# Power.net
KiCad netlist of a schematic drawn in Altium Designer
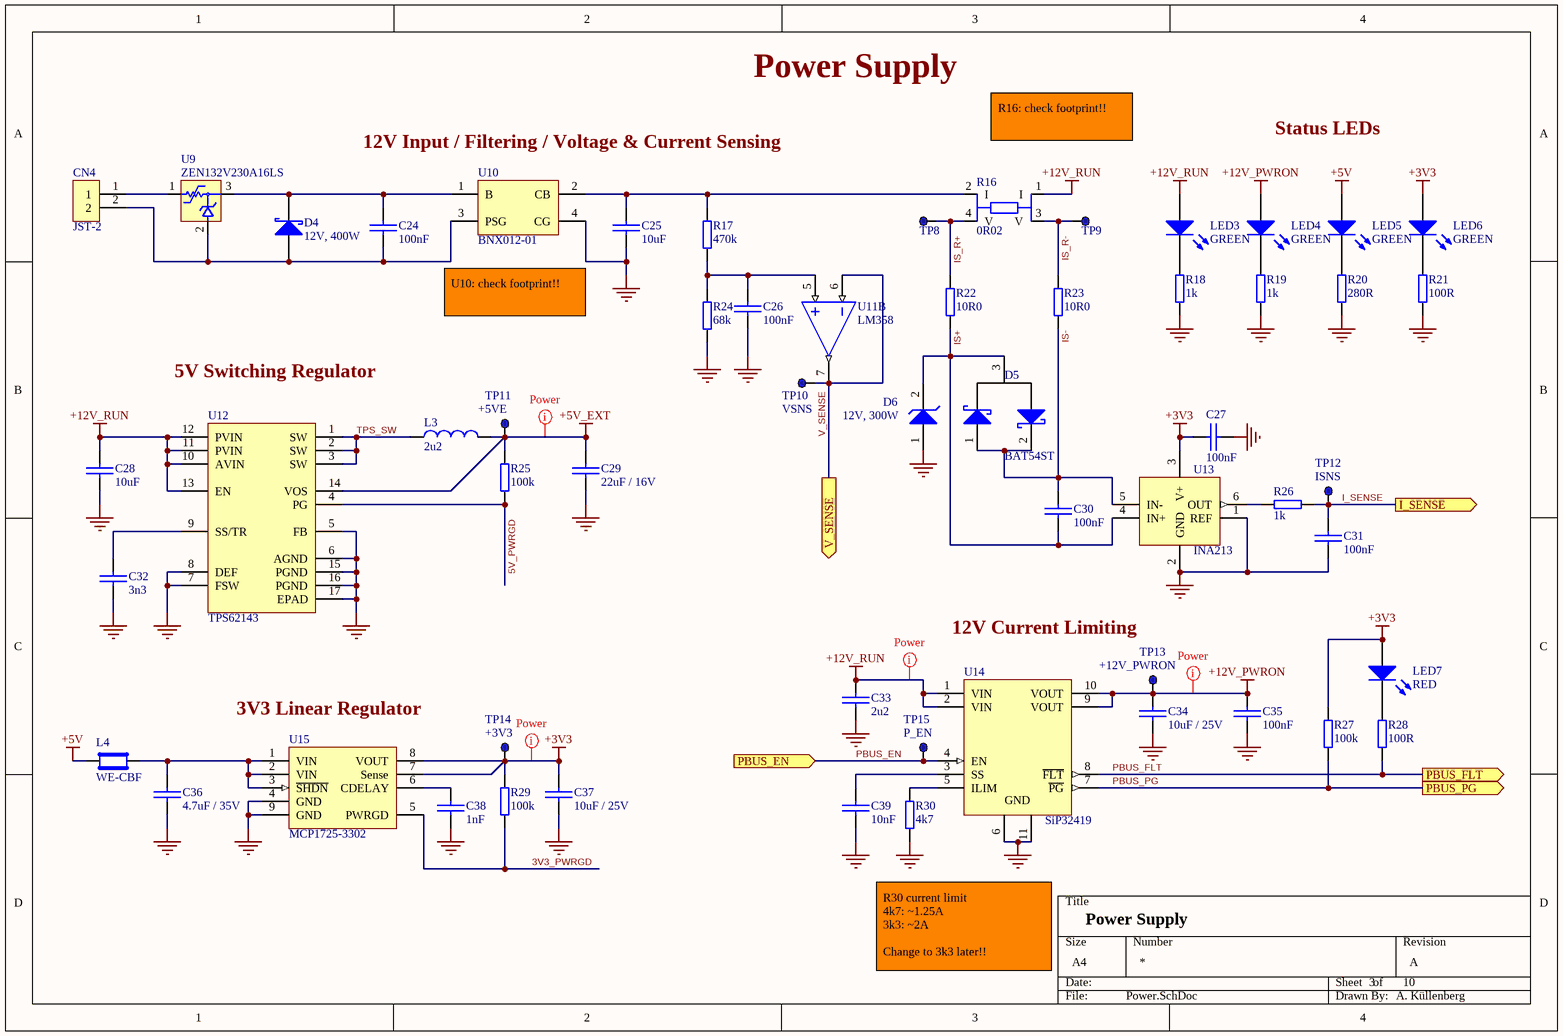
[diagram p0: Power.SchDoc]

(export (version "E")
  (design (tool "Eeschema 10.0.6"))
  (components
    (comp (ref "C24")
      (value "100nF")
      (footprint "C0805")
      (description "CAP CER 0.1UF 50V 10% X7R 0805")
      (fields (field (name "PART NUMBER") "C0805C104K5RACTU") (field (name "MANUFACTURER") "Kemet"))
      (libsource (lib "AKLib") (part "CAP"))
    )
    (comp (ref "C25")
      (value "10uF")
      (footprint "C1206")
      (description "CAP CER 10UF 35V X7R 1206")
      (fields (field (name "PART NUMBER") "GMK316AB7106KL-TR") (field (name "MANUFACTURER") "Taiyo Yuden"))
      (libsource (lib "AKLib") (part "CAP"))
    )
    (comp (ref "C26")
      (value "100nF")
      (footprint "C0603")
      (description "CAP CER 0.1UF 50V X7R 0603")
      (fields (field (name "PART NUMBER") "C0603C104K5RACTU") (field (name "MANUFACTURER") "Kemet"))
      (libsource (lib "AKLib") (part "CAP"))
    )
    (comp (ref "C27")
      (value "100nF")
      (footprint "C0603")
      (description "CAP CER 0.1UF 50V X7R 0603")
      (fields (field (name "PART NUMBER") "C0603C104K5RACTU") (field (name "MANUFACTURER") "Kemet"))
      (libsource (lib "AKLib") (part "CAP"))
    )
    (comp (ref "C28")
      (value "10uF")
      (footprint "C1206")
      (description "CAP CER 10UF 35V X7R 1206")
      (fields (field (name "PART NUMBER") "GMK316AB7106KL-TR") (field (name "MANUFACTURER") "Taiyo Yuden"))
      (libsource (lib "AKLib") (part "CAP"))
    )
    (comp (ref "C29")
      (value "22uF / 16V")
      (footprint "C0805")
      (description "CAP CER 22UF 16V X5R 0805")
      (fields
        (field (name "PART NUMBER") "C2012X5R1C226M085AC")
        (field (name "MANUFACTURER") "TDK Corporation")
      )
      (libsource (lib "AKLib") (part "CAP"))
    )
    (comp (ref "C30")
      (value "100nF")
      (footprint "C0603")
      (description "CAP CER 0.1UF 50V X7R 0603")
      (fields (field (name "PART NUMBER") "C0603C104K5RACTU") (field (name "MANUFACTURER") "Kemet"))
      (libsource (lib "AKLib") (part "CAP"))
    )
    (comp (ref "C31")
      (value "100nF")
      (footprint "C0603")
      (description "CAP CER 0.1UF 50V X7R 0603")
      (fields (field (name "PART NUMBER") "C0603C104K5RACTU") (field (name "MANUFACTURER") "Kemet"))
      (libsource (lib "AKLib") (part "CAP"))
    )
    (comp (ref "C32")
      (value "3n3")
      (footprint "C0603")
      (description "CAP CER 3300PF 50V X7R 0603")
      (fields
        (field (name "PART NUMBER") "CL10B332KB8SFNC")
        (field (name "MANUFACTURER") "Samsung Electro-Mechanics America, Inc.")
      )
      (libsource (lib "AKLib") (part "CAP"))
    )
    (comp (ref "C33")
      (value "2u2")
      (footprint "C0805")
      (description "CAP CER 2.2UF 50V X7R 0805")
      (fields (field (name "PART NUMBER") "UMK212BB7225KG-T") (field (name "MANUFACTURER") "Taiyo Yuden"))
      (libsource (lib "AKLib") (part "CAP"))
    )
    (comp (ref "C34")
      (value "10uF / 25V")
      (footprint "C0603")
      (description "CAP CER 10UF 25V X5R 0603")
      (fields
        (field (name "PART NUMBER") "ZRB18AR61E106ME01L")
        (field (name "MANUFACTURER") "Murata Electronics North America")
      )
      (libsource (lib "AKLib") (part "CAP"))
    )
    (comp (ref "C35")
      (value "100nF")
      (footprint "C0603")
      (description "CAP CER 0.1UF 50V X7R 0603")
      (fields (field (name "PART NUMBER") "C0603C104K5RACTU") (field (name "MANUFACTURER") "Kemet"))
      (libsource (lib "AKLib") (part "CAP"))
    )
    (comp (ref "C36")
      (value "4.7uF / 35V")
      (footprint "C0805")
      (description "CAP CER 4.7UF 35V X7R 0805")
      (fields
        (field (name "PART NUMBER") "C2012X7R1V475K125AE")
        (field (name "MANUFACTURER") "TDK Corporation")
      )
      (libsource (lib "AKLib") (part "CAP"))
    )
    (comp (ref "C37")
      (value "10uF / 25V")
      (footprint "C0603")
      (description "CAP CER 10UF 25V X5R 0603")
      (fields
        (field (name "PART NUMBER") "ZRB18AR61E106ME01L")
        (field (name "MANUFACTURER") "Murata Electronics North America")
      )
      (libsource (lib "AKLib") (part "CAP"))
    )
    (comp (ref "C38")
      (value "1nF")
      (footprint "C0603")
      (description "CAP CER 1000PF 50V X7R 0603")
      (fields (field (name "PART NUMBER") "C0603C102K5RACTU") (field (name "MANUFACTURER") "Kemet"))
      (libsource (lib "AKLib") (part "CAP"))
    )
    (comp (ref "C39")
      (value "10nF")
      (footprint "C0603")
      (description "CAP CER 10000PF 50V X7R 0603")
      (fields (field (name "PART NUMBER") "06035C103KAT2A") (field (name "MANUFACTURER") "AVX Corporation"))
      (libsource (lib "AKLib") (part "CAP"))
    )
    (comp (ref "CN4")
      (value "JST-2")
      (footprint "JST-2")
      (description "CONN HEADER XH TOP 2POS 2.5MM")
      (fields
        (field (name "PART NUMBER") "B2B-XH-A(LF)(SN)")
        (field (name "MANUFACTURER") "JST Sales America Inc.")
      )
      (libsource (lib "AKLib") (part "Header 1x2"))
    )
    (comp (ref "D4")
      (value "12V, 400W")
      (footprint "DO-214AC")
      (description "TVS DIODE 12VWM 25.3VC SMA")
      (fields (field (name "PART NUMBER") "SMAJ12A-TR") (field (name "MANUFACTURER") "STMicroelectronics"))
      (libsource (lib "AKLib") (part "Schottky Diode"))
    )
    (comp (ref "D5")
      (value "BAT54ST")
      (footprint "SOT-523")
      (description "DIODE ARRAY SCHOTTKY 30V SOT523")
      (fields (field (name "PART NUMBER") "BAT54ST-7-F") (field (name "MANUFACTURER") "Diodes Incorporated"))
      (libsource (lib "AKLib") (part "Diode-Dual-Anti"))
    )
    (comp (ref "D6")
      (value "12V, 300W")
      (footprint "SOD523")
      (description "TVS DIODE 12VWM 28VC SOD523")
      (fields (field (name "PART NUMBER") "T12S5-7") (field (name "MANUFACTURER") "Diodes Incorporated"))
      (libsource (lib "AKLib") (part "TVS-Uni"))
    )
    (comp (ref "L3")
      (value "2u2")
      (footprint "IHLP-1212BZ-11")
      (description "FIXED IND 2.2UH 3A 46 MOHM SMD")
      (fields (field (name "PART NUMBER") "IHLP1212BZER2R2M11") (field (name "MANUFACTURER") "Vishay Dale"))
      (libsource (lib "AKLib") (part "IND"))
    )
    (comp (ref "L4")
      (value "WE-CBF")
      (footprint "L0805")
      (description "FERRITE BEAD 600 OHM 0805 1LN")
      (fields (field (name "PART NUMBER") "742792040") (field (name "MANUFACTURER") "Wurth Electronics Inc"))
      (libsource (lib "AKLib") (part "FBEAD"))
    )
    (comp (ref "LED3")
      (value "GREEN")
      (footprint "LED_0603_GREEN")
      (description "LED GREEN CLEAR 0603 SMD")
      (fields (field (name "PART NUMBER") "LTST-C190KGKT") (field (name "MANUFACTURER") "Lite-On Inc."))
      (libsource (lib "AKLib") (part "LED"))
    )
    (comp (ref "LED4")
      (value "GREEN")
      (footprint "LED_0603_GREEN")
      (description "LED GREEN CLEAR 0603 SMD")
      (fields (field (name "PART NUMBER") "LTST-C190KGKT") (field (name "MANUFACTURER") "Lite-On Inc."))
      (libsource (lib "AKLib") (part "LED"))
    )
    (comp (ref "LED5")
      (value "GREEN")
      (footprint "LED_0603_GREEN")
      (description "LED GREEN CLEAR 0603 SMD")
      (fields (field (name "PART NUMBER") "LTST-C190KGKT") (field (name "MANUFACTURER") "Lite-On Inc."))
      (libsource (lib "AKLib") (part "LED"))
    )
    (comp (ref "LED6")
      (value "GREEN")
      (footprint "LED_0603_GREEN")
      (description "LED GREEN CLEAR 0603 SMD")
      (fields (field (name "PART NUMBER") "LTST-C190KGKT") (field (name "MANUFACTURER") "Lite-On Inc."))
      (libsource (lib "AKLib") (part "LED"))
    )
    (comp (ref "LED7")
      (value "RED")
      (footprint "LED_0603_RED")
      (description "LED RED CLEAR 0603 SMD")
      (fields (field (name "PART NUMBER") "LTST-C190KRKT") (field (name "MANUFACTURER") "Lite-On Inc."))
      (libsource (lib "AKLib") (part "LED"))
    )
    (comp (ref "R16")
      (value "0R02")
      (footprint "LVK12")
      (description "RES SMD 0.02 OHM 0.5% 1/2W 1206")
      (fields (field (name "PART NUMBER") "LVK12R020DER") (field (name "MANUFACTURER") "Ohmite"))
      (libsource (lib "AKLib") (part "RES-Kelvin"))
    )
    (comp (ref "R17")
      (value "470k")
      (footprint "R0603")
      (description "RES SMD 470K OHM 1% 1/10W 0603")
      (fields (field (name "PART NUMBER") "RC0603FR-07470KL") (field (name "MANUFACTURER") "Yageo"))
      (libsource (lib "AKLib") (part "RES"))
    )
    (comp (ref "R18")
      (value "1k")
      (footprint "R0603")
      (description "RES SMD 1K OHM 1% 1/10W 0603")
      (fields (field (name "PART NUMBER") "CRCW06031K00FKEA") (field (name "MANUFACTURER") "Vishay Dale"))
      (libsource (lib "AKLib") (part "RES"))
    )
    (comp (ref "R19")
      (value "1k")
      (footprint "R0603")
      (description "RES SMD 1K OHM 1% 1/10W 0603")
      (fields (field (name "PART NUMBER") "CRCW06031K00FKEA") (field (name "MANUFACTURER") "Vishay Dale"))
      (libsource (lib "AKLib") (part "RES"))
    )
    (comp (ref "R20")
      (value "280R")
      (footprint "R0603")
      (description "RES SMD 280 OHM 1% 1/10W 0603")
      (fields (field (name "PART NUMBER") "RC0603FR-07280RL") (field (name "MANUFACTURER") "Yageo"))
      (libsource (lib "AKLib") (part "RES"))
    )
    (comp (ref "R21")
      (value "100R")
      (footprint "R0603")
      (description "RES SMD 100 OHM 5% 1/10W 0603")
      (fields (field (name "PART NUMBER") "RC0603JR-07100RL") (field (name "MANUFACTURER") "Yageo"))
      (libsource (lib "AKLib") (part "RES"))
    )
    (comp (ref "R22")
      (value "10R0")
      (footprint "R0603")
      (description "RES SMD 10 OHM 1% 1/10W 0603")
      (fields (field (name "PART NUMBER") "CRCW060310R0FKEA") (field (name "MANUFACTURER") "Vishay Dale"))
      (libsource (lib "AKLib") (part "RES"))
    )
    (comp (ref "R23")
      (value "10R0")
      (footprint "R0603")
      (description "RES SMD 10 OHM 1% 1/10W 0603")
      (fields (field (name "PART NUMBER") "CRCW060310R0FKEA") (field (name "MANUFACTURER") "Vishay Dale"))
      (libsource (lib "AKLib") (part "RES"))
    )
    (comp (ref "R24")
      (value "68k")
      (footprint "R0603")
      (description "RES SMD 68K OHM 1% 1/10W 0603")
      (fields (field (name "PART NUMBER") "RC0603FR-0768KL") (field (name "MANUFACTURER") "Yageo"))
      (libsource (lib "AKLib") (part "RES"))
    )
    (comp (ref "R25")
      (value "100k")
      (footprint "R0603")
      (description "RES SMD 100K OHM 1% 1/10W 0603")
      (fields (field (name "PART NUMBER") "RC0603FR-07100KL") (field (name "MANUFACTURER") "Yageo"))
      (libsource (lib "AKLib") (part "RES"))
    )
    (comp (ref "R26")
      (value "1k")
      (footprint "R0603")
      (description "RES SMD 1K OHM 1% 1/10W 0603")
      (fields (field (name "PART NUMBER") "CRCW06031K00FKEA") (field (name "MANUFACTURER") "Vishay Dale"))
      (libsource (lib "AKLib") (part "RES"))
    )
    (comp (ref "R27")
      (value "100k")
      (footprint "R0603")
      (description "RES SMD 100K OHM 1% 1/10W 0603")
      (fields (field (name "PART NUMBER") "RC0603FR-07100KL") (field (name "MANUFACTURER") "Yageo"))
      (libsource (lib "AKLib") (part "RES"))
    )
    (comp (ref "R28")
      (value "100R")
      (footprint "R0603")
      (description "RES SMD 100 OHM 5% 1/10W 0603")
      (fields (field (name "PART NUMBER") "RC0603JR-07100RL") (field (name "MANUFACTURER") "Yageo"))
      (libsource (lib "AKLib") (part "RES"))
    )
    (comp (ref "R29")
      (value "100k")
      (footprint "R0603")
      (description "RES SMD 100K OHM 1% 1/10W 0603")
      (fields (field (name "PART NUMBER") "RC0603FR-07100KL") (field (name "MANUFACTURER") "Yageo"))
      (libsource (lib "AKLib") (part "RES"))
    )
    (comp (ref "R30")
      (value "4k7")
      (footprint "R0603")
      (description "RES SMD 4.7K OHM 1% 1/10W 0603")
      (fields (field (name "PART NUMBER") "CRCW06034K70FKEA") (field (name "MANUFACTURER") "Vishay Dale"))
      (libsource (lib "AKLib") (part "RES"))
    )
    (comp (ref "TP8")
      (value "ISR+")
      (footprint "TP_1mm")
      (fields (field (name "PART NUMBER") "TP"))
      (libsource (lib "AKLib") (part "TP"))
    )
    (comp (ref "TP9")
      (value "ISR-")
      (footprint "TP_1mm")
      (fields (field (name "PART NUMBER") "TP"))
      (libsource (lib "AKLib") (part "TP"))
    )
    (comp (ref "TP10")
      (value "VSNS")
      (footprint "TP_1mm")
      (fields (field (name "PART NUMBER") "TP"))
      (libsource (lib "AKLib") (part "TP"))
    )
    (comp (ref "TP11")
      (value "+5VE")
      (footprint "TP_1mm")
      (fields (field (name "PART NUMBER") "TP"))
      (libsource (lib "AKLib") (part "TP"))
    )
    (comp (ref "TP12")
      (value "ISNS")
      (footprint "TP_1mm")
      (fields (field (name "PART NUMBER") "TP"))
      (libsource (lib "AKLib") (part "TP"))
    )
    (comp (ref "TP13")
      (value "+12V_PWRON")
      (footprint "TP_1mm")
      (fields (field (name "PART NUMBER") "TP"))
      (libsource (lib "AKLib") (part "TP"))
    )
    (comp (ref "TP14")
      (value "+3V3")
      (footprint "TP_1mm")
      (fields (field (name "PART NUMBER") "TP"))
      (libsource (lib "AKLib") (part "TP"))
    )
    (comp (ref "TP15")
      (value "P_EN")
      (footprint "TP_1mm")
      (fields (field (name "PART NUMBER") "TP"))
      (libsource (lib "AKLib") (part "TP"))
    )
    (comp (ref "U9")
      (value "ZEN132V230A16LS")
      (footprint "ZEN132V230A16LS")
      (description "POLYZEN 13.2V PPTC/ZENER SMD")
      (fields (field (name "MANUFACTURER") "Littelfuse Inc."))
      (libsource (lib "AKLib") (part "PolyZen"))
    )
    (comp (ref "U10")
      (value "BNX012-01")
      (footprint "BNX012-01")
      (description "FILTER LC TH")
      (fields (field (name "MANUFACTURER") "Murata Electronics North America"))
      (libsource (lib "AKLib") (part "BNX012-01"))
    )
    (comp (ref "U11")
      (value "LM358")
      (footprint "DFN 2x2_LM358")
      (description "IC OPAMP GP 1.1MHZ 8DFN")
      (fields (field (name "PART NUMBER") "LM358QT") (field (name "MANUFACTURER") "STMicroelectronics"))
      (libsource (lib "AKLib") (part "LM358"))
    )
    (comp (ref "U12")
      (value "TPS62143")
      (footprint "RGT0016C")
      (description "IC REG BUCK 5V 2A SYNC 16QFN")
      (fields (field (name "PART NUMBER") "TPS62143RGTR") (field (name "MANUFACTURER") "Texas Instruments"))
      (libsource (lib "AKLib") (part "TPS6214x"))
    )
    (comp (ref "U13")
      (value "INA213")
      (footprint "SC-70-6")
      (description "IC OPAMP CURR SENSE 14KHZ SC70-6")
      (fields (field (name "PART NUMBER") "INA213BIDCKR") (field (name "MANUFACTURER") "Texas Instruments"))
      (libsource (lib "AKLib") (part "INA21x"))
    )
    (comp (ref "U14")
      (value "SiP32419")
      (footprint "DFN 3x3_SiP324x9")
      (description "LOAD SWITCH 3A 28V 10DFN")
      (fields
        (field (name "PART NUMBER") "SIP32419DN-T1-GE4")
        (field (name "MANUFACTURER") "Vishay Siliconix")
      )
      (libsource (lib "AKLib") (part "SiP324x9"))
    )
    (comp (ref "U15")
      (value "MCP1725-3302")
      (footprint "QFN50P200X300X100_HS-9N")
      (description "IC REG LDO 3.3V 0.5A 8DFN")
      (fields
        (field (name "PART NUMBER") "MCP1725-3302E/MC")
        (field (name "MANUFACTURER") "Microchip Technology")
      )
      (libsource (lib "AKLib") (part "MCP1725_fixed"))
    )
  )
  (nets
    (net (code "1") (name "+3V3") (class "Default")
      (node (ref "C27") (pin "1") (pinfunction "1_1") (pintype "passive"))
      (node (ref "C37") (pin "2") (pinfunction "2_2") (pintype "passive"))
      (node (ref "LED6") (pin "1") (pinfunction "A_1") (pintype "passive"))
      (node (ref "LED7") (pin "1") (pinfunction "A_1") (pintype "passive"))
      (node (ref "R27") (pin "2") (pinfunction "2_2") (pintype "passive"))
      (node (ref "R29") (pin "2") (pinfunction "2_2") (pintype "passive"))
      (node (ref "TP14") (pin "1") (pinfunction "1_1") (pintype "passive"))
      (node (ref "U13") (pin "3") (pinfunction "V+_3") (pintype "power_in"))
      (node (ref "U15") (pin "7") (pinfunction "Sense_7") (pintype "passive"))
      (node (ref "U15") (pin "8") (pinfunction "VOUT_8") (pintype "power_in"))
    )
    (net (code "2") (name "+5V") (class "Default")
      (node (ref "L4") (pin "1") (pinfunction "1_1") (pintype "passive"))
      (node (ref "LED5") (pin "1") (pinfunction "A_1") (pintype "passive"))
    )
    (net (code "3") (name "+5V_EXT") (class "Default")
      (node (ref "C29") (pin "2") (pinfunction "2_2") (pintype "passive"))
      (node (ref "L3") (pin "2") (pinfunction "2_2") (pintype "passive"))
      (node (ref "R25") (pin "2") (pinfunction "2_2") (pintype "passive"))
      (node (ref "TP11") (pin "1") (pinfunction "1_1") (pintype "passive"))
      (node (ref "U12") (pin "14") (pinfunction "VOS_14") (pintype "passive"))
    )
    (net (code "4") (name "+12V_PWRON") (class "Default")
      (node (ref "C34") (pin "2") (pinfunction "2_2") (pintype "passive"))
      (node (ref "C35") (pin "2") (pinfunction "2_2") (pintype "passive"))
      (node (ref "LED4") (pin "1") (pinfunction "A_1") (pintype "passive"))
      (node (ref "TP13") (pin "1") (pinfunction "1_1") (pintype "passive"))
      (node (ref "U14") (pin "10") (pinfunction "VOUT_10") (pintype "power_in"))
      (node (ref "U14") (pin "9") (pinfunction "VOUT_9") (pintype "power_in"))
    )
    (net (code "5") (name "+12V_RUN") (class "Default")
      (node (ref "C28") (pin "2") (pinfunction "2_2") (pintype "passive"))
      (node (ref "C33") (pin "2") (pinfunction "2_2") (pintype "passive"))
      (node (ref "LED3") (pin "1") (pinfunction "A_1") (pintype "passive"))
      (node (ref "R16") (pin "1") (pinfunction "I_1") (pintype "passive"))
      (node (ref "U12") (pin "10") (pinfunction "AVIN_10") (pintype "passive"))
      (node (ref "U12") (pin "11") (pinfunction "PVIN_11") (pintype "passive"))
      (node (ref "U12") (pin "12") (pinfunction "PVIN_12") (pintype "passive"))
      (node (ref "U12") (pin "13") (pinfunction "EN_13") (pintype "passive"))
      (node (ref "U14") (pin "1") (pinfunction "VIN_1") (pintype "power_in"))
      (node (ref "U14") (pin "2") (pinfunction "VIN_2") (pintype "power_in"))
    )
    (net (code "6") (name "/3V3_PWRGD") (class "Default")
      (node (ref "R29") (pin "1") (pinfunction "1_1") (pintype "passive"))
      (node (ref "U15") (pin "5") (pinfunction "PWRGD_5") (pintype "open_collector"))
    )
    (net (code "7") (name "/5V_PWRGD") (class "Default")
      (node (ref "R25") (pin "1") (pinfunction "1_1") (pintype "passive"))
      (node (ref "U12") (pin "4") (pinfunction "PG_4") (pintype "passive"))
    )
    (net (code "8") (name "/IS+") (class "Default")
      (node (ref "C30") (pin "1") (pinfunction "1_1") (pintype "passive"))
      (node (ref "D5") (pin "3") (pinfunction "COM_3") (pintype "passive"))
      (node (ref "D6") (pin "2") (pinfunction "K_2") (pintype "passive"))
      (node (ref "R22") (pin "1") (pinfunction "1_1") (pintype "passive"))
      (node (ref "U13") (pin "4") (pinfunction "IN+_4") (pintype "passive"))
    )
    (net (code "9") (name "/IS-") (class "Default")
      (node (ref "C30") (pin "2") (pinfunction "2_2") (pintype "passive"))
      (node (ref "D5") (pin "1") (pinfunction "A_1") (pintype "passive"))
      (node (ref "D5") (pin "2") (pinfunction "K_2") (pintype "passive"))
      (node (ref "R23") (pin "1") (pinfunction "1_1") (pintype "passive"))
      (node (ref "U13") (pin "5") (pinfunction "IN-_5") (pintype "passive"))
    )
    (net (code "10") (name "/IS_R+") (class "Default")
      (node (ref "R16") (pin "4") (pinfunction "V_4") (pintype "power_in"))
      (node (ref "R22") (pin "2") (pinfunction "2_2") (pintype "passive"))
      (node (ref "TP8") (pin "1") (pinfunction "1_1") (pintype "passive"))
    )
    (net (code "11") (name "/IS_R-") (class "Default")
      (node (ref "R16") (pin "3") (pinfunction "V_3") (pintype "power_in"))
      (node (ref "R23") (pin "2") (pinfunction "2_2") (pintype "passive"))
      (node (ref "TP9") (pin "1") (pinfunction "1_1") (pintype "passive"))
    )
    (net (code "12") (name "/I_SENSE") (class "Default")
      (node (ref "C31") (pin "2") (pinfunction "2_2") (pintype "passive"))
      (node (ref "R26") (pin "2") (pinfunction "2_2") (pintype "passive"))
      (node (ref "TP12") (pin "1") (pinfunction "1_1") (pintype "passive"))
    )
    (net (code "13") (name "/PBUS_EN") (class "Default")
      (node (ref "TP15") (pin "1") (pinfunction "1_1") (pintype "passive"))
      (node (ref "U14") (pin "4") (pinfunction "EN_4") (pintype "input"))
    )
    (net (code "14") (name "/PBUS_FLT") (class "Default")
      (node (ref "R28") (pin "1") (pinfunction "1_1") (pintype "passive"))
      (node (ref "U14") (pin "8") (pinfunction "~{FLT}_8") (pintype "output"))
    )
    (net (code "15") (name "/PBUS_PG") (class "Default")
      (node (ref "R27") (pin "1") (pinfunction "1_1") (pintype "passive"))
      (node (ref "U14") (pin "7") (pinfunction "~{PG}_7") (pintype "output"))
    )
    (net (code "16") (name "/TPS_SW") (class "Default")
      (node (ref "L3") (pin "1") (pinfunction "1_1") (pintype "passive"))
      (node (ref "U12") (pin "1") (pinfunction "SW_1") (pintype "passive"))
      (node (ref "U12") (pin "2") (pinfunction "SW_2") (pintype "passive"))
      (node (ref "U12") (pin "3") (pinfunction "SW_3") (pintype "passive"))
    )
    (net (code "17") (name "/V_SENSE") (class "Default")
      (node (ref "TP10") (pin "1") (pinfunction "1_1") (pintype "passive"))
      (node (ref "U11") (pin "6") (pinfunction "IN-_6") (pintype "input"))
      (node (ref "U11") (pin "7") (pinfunction "OUT_7") (pintype "output"))
    )
    (net (code "18") (name "GND") (class "Default")
      (node (ref "C25") (pin "1") (pinfunction "1_1") (pintype "passive"))
      (node (ref "C26") (pin "1") (pinfunction "1_1") (pintype "passive"))
      (node (ref "C27") (pin "2") (pinfunction "2_2") (pintype "passive"))
      (node (ref "C28") (pin "1") (pinfunction "1_1") (pintype "passive"))
      (node (ref "C29") (pin "1") (pinfunction "1_1") (pintype "passive"))
      (node (ref "C31") (pin "1") (pinfunction "1_1") (pintype "passive"))
      (node (ref "C32") (pin "1") (pinfunction "1_1") (pintype "passive"))
      (node (ref "C33") (pin "1") (pinfunction "1_1") (pintype "passive"))
      (node (ref "C34") (pin "1") (pinfunction "1_1") (pintype "passive"))
      (node (ref "C35") (pin "1") (pinfunction "1_1") (pintype "passive"))
      (node (ref "C36") (pin "1") (pinfunction "1_1") (pintype "passive"))
      (node (ref "C37") (pin "1") (pinfunction "1_1") (pintype "passive"))
      (node (ref "C38") (pin "1") (pinfunction "1_1") (pintype "passive"))
      (node (ref "C39") (pin "1") (pinfunction "1_1") (pintype "passive"))
      (node (ref "D6") (pin "1") (pinfunction "A_1") (pintype "passive"))
      (node (ref "R18") (pin "1") (pinfunction "1_1") (pintype "passive"))
      (node (ref "R19") (pin "1") (pinfunction "1_1") (pintype "passive"))
      (node (ref "R20") (pin "1") (pinfunction "1_1") (pintype "passive"))
      (node (ref "R21") (pin "1") (pinfunction "1_1") (pintype "passive"))
      (node (ref "R24") (pin "1") (pinfunction "1_1") (pintype "passive"))
      (node (ref "R30") (pin "1") (pinfunction "1_1") (pintype "passive"))
      (node (ref "U10") (pin "4") (pinfunction "CG_4") (pintype "passive"))
      (node (ref "U12") (pin "15") (pinfunction "PGND_15") (pintype "passive"))
      (node (ref "U12") (pin "16") (pinfunction "PGND_16") (pintype "passive"))
      (node (ref "U12") (pin "17") (pinfunction "EPAD_17") (pintype "passive"))
      (node (ref "U12") (pin "5") (pinfunction "FB_5") (pintype "passive"))
      (node (ref "U12") (pin "6") (pinfunction "AGND_6") (pintype "passive"))
      (node (ref "U12") (pin "7") (pinfunction "FSW_7") (pintype "passive"))
      (node (ref "U12") (pin "8") (pinfunction "DEF_8") (pintype "passive"))
      (node (ref "U13") (pin "1") (pinfunction "REF_1") (pintype "passive"))
      (node (ref "U13") (pin "2") (pinfunction "GND_2") (pintype "power_in"))
      (node (ref "U14") (pin "11") (pinfunction "GND_11") (pintype "power_in"))
      (node (ref "U14") (pin "6") (pinfunction "GND_6") (pintype "power_in"))
      (node (ref "U15") (pin "4") (pinfunction "GND_4") (pintype "power_in"))
      (node (ref "U15") (pin "9") (pinfunction "GND_9") (pintype "power_in"))
    )
    (net (code "19") (name "Net-(CN4-Pad1)") (class "Default")
      (node (ref "CN4") (pin "1") (pinfunction "1_1") (pintype "passive"))
      (node (ref "U9") (pin "1") (pintype "passive"))
    )
    (net (code "20") (name "Net-(D4-A)") (class "Default")
      (node (ref "C24") (pin "1") (pinfunction "1_1") (pintype "passive"))
      (node (ref "CN4") (pin "2") (pinfunction "2_2") (pintype "passive"))
      (node (ref "D4") (pin "1") (pinfunction "A_1") (pintype "passive"))
      (node (ref "U10") (pin "3") (pinfunction "PSG_3") (pintype "passive"))
      (node (ref "U9") (pin "2") (pintype "passive"))
    )
    (net (code "21") (name "Net-(D4-K)") (class "Default")
      (node (ref "C24") (pin "2") (pinfunction "2_2") (pintype "passive"))
      (node (ref "D4") (pin "2") (pinfunction "K_2") (pintype "passive"))
      (node (ref "U10") (pin "1") (pinfunction "B_1") (pintype "passive"))
      (node (ref "U9") (pin "3") (pintype "passive"))
    )
    (net (code "22") (name "Net-(LED3-K)") (class "Default")
      (node (ref "LED3") (pin "2") (pinfunction "K_2") (pintype "passive"))
      (node (ref "R18") (pin "2") (pinfunction "2_2") (pintype "passive"))
    )
    (net (code "23") (name "Net-(LED4-K)") (class "Default")
      (node (ref "LED4") (pin "2") (pinfunction "K_2") (pintype "passive"))
      (node (ref "R19") (pin "2") (pinfunction "2_2") (pintype "passive"))
    )
    (net (code "24") (name "Net-(LED5-K)") (class "Default")
      (node (ref "LED5") (pin "2") (pinfunction "K_2") (pintype "passive"))
      (node (ref "R20") (pin "2") (pinfunction "2_2") (pintype "passive"))
    )
    (net (code "25") (name "Net-(LED6-K)") (class "Default")
      (node (ref "LED6") (pin "2") (pinfunction "K_2") (pintype "passive"))
      (node (ref "R21") (pin "2") (pinfunction "2_2") (pintype "passive"))
    )
    (net (code "26") (name "Net-(LED7-K)") (class "Default")
      (node (ref "LED7") (pin "2") (pinfunction "K_2") (pintype "passive"))
      (node (ref "R28") (pin "2") (pinfunction "2_2") (pintype "passive"))
    )
    (net (code "27") (name "Net-(U10-CB)") (class "Default")
      (node (ref "C25") (pin "2") (pinfunction "2_2") (pintype "passive"))
      (node (ref "R16") (pin "2") (pinfunction "I_2") (pintype "passive"))
      (node (ref "R17") (pin "2") (pinfunction "2_2") (pintype "passive"))
      (node (ref "U10") (pin "2") (pinfunction "CB_2") (pintype "passive"))
    )
    (net (code "28") (name "Net-(U11B-IN+)") (class "Default")
      (node (ref "C26") (pin "2") (pinfunction "2_2") (pintype "passive"))
      (node (ref "R17") (pin "1") (pinfunction "1_1") (pintype "passive"))
      (node (ref "R24") (pin "2") (pinfunction "2_2") (pintype "passive"))
      (node (ref "U11") (pin "5") (pinfunction "IN+_5") (pintype "input"))
    )
    (net (code "29") (name "Net-(U12-SS{slash}TR)") (class "Default")
      (node (ref "C32") (pin "2") (pinfunction "2_2") (pintype "passive"))
      (node (ref "U12") (pin "9") (pinfunction "SS/TR_9") (pintype "passive"))
    )
    (net (code "30") (name "Net-(U13-OUT)") (class "Default")
      (node (ref "R26") (pin "1") (pinfunction "1_1") (pintype "passive"))
      (node (ref "U13") (pin "6") (pinfunction "OUT_6") (pintype "output"))
    )
    (net (code "31") (name "Net-(U14-ILIM)") (class "Default")
      (node (ref "R30") (pin "2") (pinfunction "2_2") (pintype "passive"))
      (node (ref "U14") (pin "5") (pinfunction "ILIM_5") (pintype "passive"))
    )
    (net (code "32") (name "Net-(U14-SS)") (class "Default")
      (node (ref "C39") (pin "2") (pinfunction "2_2") (pintype "passive"))
      (node (ref "U14") (pin "3") (pinfunction "SS_3") (pintype "passive"))
    )
    (net (code "33") (name "Net-(U15-CDELAY)") (class "Default")
      (node (ref "C38") (pin "2") (pinfunction "2_2") (pintype "passive"))
      (node (ref "U15") (pin "6") (pinfunction "CDELAY_6") (pintype "passive"))
    )
    (net (code "34") (name "Net-(U15-~{SHDN})") (class "Default")
      (node (ref "C36") (pin "2") (pinfunction "2_2") (pintype "passive"))
      (node (ref "L4") (pin "2") (pinfunction "2_2") (pintype "passive"))
      (node (ref "U15") (pin "1") (pinfunction "VIN_1") (pintype "power_in"))
      (node (ref "U15") (pin "2") (pinfunction "VIN_2") (pintype "power_in"))
      (node (ref "U15") (pin "3") (pinfunction "~{SHDN}_3") (pintype "input"))
    )
  )
)
